# commande.net
KiCad netlist of a schematic drawn in Altium Designer
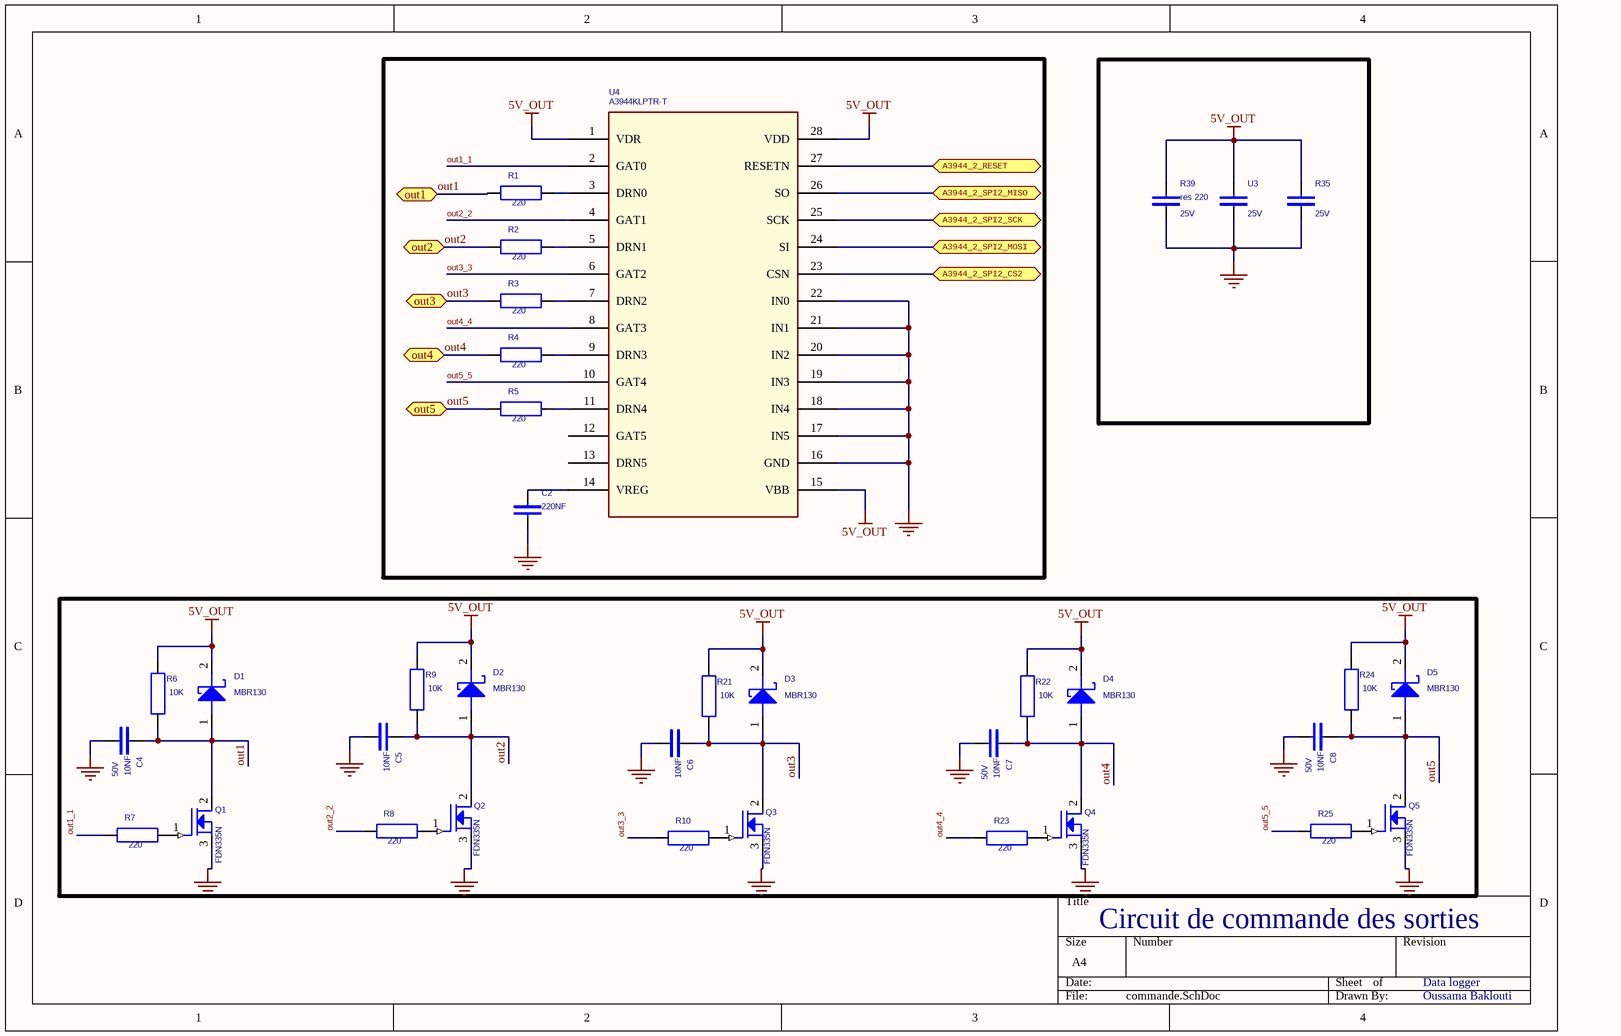
[diagram p0: commande.SchDoc]

(export (version "E")
  (design (tool "Eeschema 10.0.6"))
  (components
    (comp (ref "C2")
      (value "220NF")
      (footprint "cap 220uF 50v")
      (description "Aluminium Electrolytic Capacitors - SMD 50volts 0.22uF AEC-Q200")
      (fields (field (name "MFR") "Nichicon"))
      (libsource (lib "*") (part "CAPA_Dup1"))
    )
    (comp (ref "C4")
      (value "10NF")
      (footprint "cap 10nF 50V")
      (description "10000 pF ±10% 50V Ceramic Capacitor X7R 0402 (1005 Metric)")
      (fields
        (field (name "VOLTAGE") "50V")
        (field (name "PART NUMBER") "AY15800014")
        (field (name "TOLERANCE") "10%")
      )
      (libsource (lib "*") (part "CAPA_Dup1"))
    )
    (comp (ref "C5")
      (value "10NF")
      (footprint "cap 10nF 50V")
      (description "10000 pF ±10% 50V Ceramic Capacitor X7R 0402 (1005 Metric)")
      (fields (field (name "MFR") "Murata Electronics"))
      (libsource (lib "*") (part "CAPA_Dup1"))
    )
    (comp (ref "C6")
      (value "10NF")
      (footprint "cap 10nF 50V")
      (description "10000 pF ±10% 50V Ceramic Capacitor X7R 0402 (1005 Metric)")
      (fields (field (name "MFR") "Murata Electronics"))
      (libsource (lib "*") (part "CAPA_Dup1"))
    )
    (comp (ref "C7")
      (value "10NF")
      (footprint "cap 10nF 50V")
      (description "10000 pF ±10% 50V Ceramic Capacitor X7R 0402 (1005 Metric)")
      (fields
        (field (name "VOLTAGE") "50V")
        (field (name "PART NUMBER") "AY15800014")
        (field (name "TOLERANCE") "10%")
      )
      (libsource (lib "*") (part "CAPA_Dup1"))
    )
    (comp (ref "C8")
      (value "10NF")
      (footprint "cap 10nF 50V")
      (description "10000 pF ±10% 50V Ceramic Capacitor X7R 0402 (1005 Metric)")
      (fields
        (field (name "VOLTAGE") "50V")
        (field (name "PART NUMBER") "AY15800014")
        (field (name "TOLERANCE") "10%")
      )
      (libsource (lib "*") (part "CAPA_Dup1"))
    )
    (comp (ref "D1")
      (value "MBR130")
      (footprint "diode skotty")
      (description "Schottky Diodes & Rectifiers 1A 30V")
      (fields (field (name "MFR") "onsemi"))
      (libsource (lib "*") (part "DIODE_SCHOT"))
    )
    (comp (ref "D2")
      (value "MBR130")
      (footprint "diode skotty")
      (description "Schottky Diodes & Rectifiers 1A 30V")
      (fields (field (name "MFR") "onsemi"))
      (libsource (lib "*") (part "DIODE_SCHOT"))
    )
    (comp (ref "D3")
      (value "MBR130")
      (footprint "diode skotty")
      (description "Schottky Diodes & Rectifiers 1A 30V")
      (fields (field (name "MFR") "onsemi"))
      (libsource (lib "*") (part "DIODE_SCHOT"))
    )
    (comp (ref "D4")
      (value "MBR130")
      (footprint "diode skotty")
      (description "Schottky Diodes & Rectifiers 1A 30V")
      (fields (field (name "MFR") "onsemi"))
      (libsource (lib "*") (part "DIODE_SCHOT"))
    )
    (comp (ref "D5")
      (value "MBR130")
      (footprint "diode skotty")
      (description "Schottky Diodes & Rectifiers 1A 30V")
      (fields (field (name "MFR") "onsemi"))
      (libsource (lib "*") (part "DIODE_SCHOT"))
    )
    (comp (ref "Q1")
      (value "FDN335N")
      (footprint "FDN335N")
      (description "MOSFET SSOT-3 N-CH 20V")
      (fields (field (name "MFR") "onsemi / Fairchild"))
      (libsource (lib "*") (part "MOSFET N"))
    )
    (comp (ref "Q2")
      (value "FDN335N")
      (footprint "FDN335N")
      (description "MOSFET SSOT-3 N-CH 20V")
      (fields (field (name "MFR") "onsemi / Fairchild"))
      (libsource (lib "*") (part "MOSFET N"))
    )
    (comp (ref "Q3")
      (value "FDN335N")
      (footprint "FDN335N")
      (description "MOSFET SSOT-3 N-CH 20V")
      (fields (field (name "MFR") "onsemi / Fairchild"))
      (libsource (lib "*") (part "MOSFET N"))
    )
    (comp (ref "Q4")
      (value "FDN335N")
      (footprint "FDN335N")
      (description "MOSFET SSOT-3 N-CH 20V")
      (fields (field (name "MFR") "onsemi / Fairchild"))
      (libsource (lib "*") (part "MOSFET N"))
    )
    (comp (ref "Q5")
      (value "FDN335N")
      (footprint "FDN335N")
      (description "MOSFET SSOT-3 N-CH 20V")
      (fields (field (name "MFR") "onsemi / Fairchild"))
      (libsource (lib "*") (part "MOSFET N"))
    )
    (comp (ref "R1")
      (value "220")
      (footprint "res 220")
      (description "Thick Film Resistors - SMD 1/2watt 220ohms 1% High Power AEC-Q200")
      (fields (field (name "MFR") "Vishay / Dale"))
      (libsource (lib "*") (part "RE"))
    )
    (comp (ref "R2")
      (value "220")
      (footprint "res 220")
      (description "Thick Film Resistors - SMD 1/2watt 220ohms 1% High Power AEC-Q200")
      (fields (field (name "MFR") "Vishay / Dale"))
      (libsource (lib "*") (part "RE"))
    )
    (comp (ref "R3")
      (value "220")
      (footprint "res 220")
      (description "Thick Film Resistors - SMD 1/2watt 220ohms 1% High Power AEC-Q200")
      (fields (field (name "MFR") "Vishay / Dale"))
      (libsource (lib "*") (part "RE"))
    )
    (comp (ref "R4")
      (value "220")
      (footprint "res 220")
      (description "Thick Film Resistors - SMD 1/2watt 220ohms 1% High Power AEC-Q200")
      (fields (field (name "MFR") "Vishay / Dale"))
      (libsource (lib "*") (part "RE"))
    )
    (comp (ref "R5")
      (value "220")
      (footprint "res 220")
      (description "Thick Film Resistors - SMD 1/2watt 220ohms 1% High Power AEC-Q200")
      (fields (field (name "MFR") "Vishay / Dale"))
      (libsource (lib "*") (part "RE"))
    )
    (comp (ref "R6")
      (value "10K")
      (footprint "RES_10k")
      (description "Thick Film Resistors - SMD ResHighPowerA 0805 10k 1% 1/2W TC100")
      (fields (field (name "MFR") "Bourns"))
      (libsource (lib "*") (part "RE"))
    )
    (comp (ref "R7")
      (value "220")
      (footprint "res 220")
      (description "Thick Film Resistors - SMD 1/2watt 220ohms 1% High Power AEC-Q200")
      (fields (field (name "MFR") "Vishay / Dale"))
      (libsource (lib "*") (part "RE"))
    )
    (comp (ref "R8")
      (value "220")
      (footprint "res 220")
      (description "Thick Film Resistors - SMD 1/2watt 220ohms 1% High Power AEC-Q200")
      (fields (field (name "MFR") "Vishay / Dale"))
      (libsource (lib "*") (part "RE"))
    )
    (comp (ref "R9")
      (value "10K")
      (footprint "RES_10k")
      (description "Thick Film Resistors - SMD ResHighPowerA 0805 10k 1% 1/2W TC100")
      (fields (field (name "MFR") "Bourns"))
      (libsource (lib "*") (part "RE"))
    )
    (comp (ref "R10")
      (value "220")
      (footprint "res 220")
      (description "Thick Film Resistors - SMD 1/2watt 220ohms 1% High Power AEC-Q200")
      (fields (field (name "MFR") "Vishay / Dale"))
      (libsource (lib "*") (part "RE"))
    )
    (comp (ref "R21")
      (value "10K")
      (footprint "RES_10k")
      (description "Thick Film Resistors - SMD ResHighPowerA 0805 10k 1% 1/2W TC100")
      (fields (field (name "MFR") "Bourns"))
      (libsource (lib "*") (part "RE"))
    )
    (comp (ref "R22")
      (value "10K")
      (footprint "RES_10k")
      (description "Thick Film Resistors - SMD ResHighPowerA 0805 10k 1% 1/2W TC100")
      (fields (field (name "MFR") "Bourns"))
      (libsource (lib "*") (part "RE"))
    )
    (comp (ref "R23")
      (value "220")
      (footprint "res 220")
      (description "Thick Film Resistors - SMD 1/2watt 220ohms 1% High Power AEC-Q200")
      (fields (field (name "MFR") "Vishay / Dale"))
      (libsource (lib "*") (part "RE"))
    )
    (comp (ref "R24")
      (value "10K")
      (footprint "RES_10k")
      (description "Thick Film Resistors - SMD ResHighPowerA 0805 10k 1% 1/2W TC100")
      (fields (field (name "MFR") "Bourns"))
      (libsource (lib "*") (part "RE"))
    )
    (comp (ref "R25")
      (value "220")
      (footprint "res 220")
      (description "Thick Film Resistors - SMD 1/2watt 220ohms 1% High Power AEC-Q200")
      (fields (field (name "MFR") "Vishay / Dale"))
      (libsource (lib "*") (part "RE"))
    )
    (comp (ref "R35")
      (value "~")
      (footprint "RES 220")
      (fields
        (field (name "VOLTAGE") "25V")
        (field (name "TOLERANCE") "10%")
        (field (name "PART NUMBER") "AY15620002")
      )
      (libsource (lib "*") (part "CAPA_Dup1"))
    )
    (comp (ref "R39")
      (value "res 220")
      (footprint "RES 220")
      (fields
        (field (name "VOLTAGE") "25V")
        (field (name "TOLERANCE") "10%")
        (field (name "PART NUMBER") "AY15510021")
      )
      (libsource (lib "*") (part "CAPA_Dup1"))
    )
    (comp (ref "U3")
      (value "~")
      (footprint "LILYGO-T-CALL-SIM800L")
      (fields
        (field (name "VOLTAGE") "25V")
        (field (name "TOLERANCE") "10%")
        (field (name "PART NUMBER") "AY15620002")
      )
      (libsource (lib "*") (part "CAPA_Dup1"))
    )
    (comp (ref "U4")
      (value "A3944KLPTR-T")
      (footprint "SOP65P640X265_HS-29N")
      (description "Motor/Motion/Ignition Controllers & Drivers AUTOMOTIVE SIX CHANNEL LOW SIDE MOSFET PRE-DRIVER")
      (fields (field (name "MFR") "Mfr.:Allegro MicroSystems"))
      (libsource (lib "*") (part "A3944KLPTR-T"))
    )
  )
  (nets
    (net (code "1") (name "/A3944_2_RESET") (class "Default")
      (node (ref "U4") (pin "27") (pinfunction "RESETN_27") (pintype "passive"))
    )
    (net (code "2") (name "/A3944_2_SPI2_CS2") (class "Default")
      (node (ref "U4") (pin "23") (pinfunction "CSN_23") (pintype "passive"))
    )
    (net (code "3") (name "/A3944_2_SPI2_MISO") (class "Default")
      (node (ref "U4") (pin "26") (pinfunction "SO_26") (pintype "passive"))
    )
    (net (code "4") (name "/A3944_2_SPI2_MOSI") (class "Default")
      (node (ref "U4") (pin "24") (pinfunction "SI_24") (pintype "passive"))
    )
    (net (code "5") (name "/A3944_2_SPI2_SCK") (class "Default")
      (node (ref "U4") (pin "25") (pinfunction "SCK_25") (pintype "passive"))
    )
    (net (code "6") (name "/out1") (class "Default")
      (node (ref "C4") (pin "1") (pinfunction "1_1") (pintype "passive"))
      (node (ref "D1") (pin "1") (pinfunction "A_1") (pintype "passive"))
      (node (ref "Q1") (pin "2") (pinfunction "DRAIN_2") (pintype "passive"))
      (node (ref "R1") (pin "2") (pinfunction "2_2") (pintype "passive"))
      (node (ref "R6") (pin "2") (pinfunction "2_2") (pintype "passive"))
    )
    (net (code "7") (name "/out1_1") (class "Default")
      (node (ref "R7") (pin "2") (pinfunction "2_2") (pintype "passive"))
      (node (ref "U4") (pin "2") (pinfunction "GAT0_2") (pintype "passive"))
    )
    (net (code "8") (name "/out2") (class "Default")
      (node (ref "C5") (pin "1") (pinfunction "1_1") (pintype "passive"))
      (node (ref "D2") (pin "1") (pinfunction "A_1") (pintype "passive"))
      (node (ref "Q2") (pin "2") (pinfunction "DRAIN_2") (pintype "passive"))
      (node (ref "R2") (pin "2") (pinfunction "2_2") (pintype "passive"))
      (node (ref "R9") (pin "2") (pinfunction "2_2") (pintype "passive"))
    )
    (net (code "9") (name "/out2_2") (class "Default")
      (node (ref "R8") (pin "2") (pinfunction "2_2") (pintype "passive"))
      (node (ref "U4") (pin "4") (pinfunction "GAT1_4") (pintype "passive"))
    )
    (net (code "10") (name "/out3") (class "Default")
      (node (ref "C6") (pin "1") (pinfunction "1_1") (pintype "passive"))
      (node (ref "D3") (pin "1") (pinfunction "A_1") (pintype "passive"))
      (node (ref "Q3") (pin "2") (pinfunction "DRAIN_2") (pintype "passive"))
      (node (ref "R21") (pin "2") (pinfunction "2_2") (pintype "passive"))
      (node (ref "R3") (pin "2") (pinfunction "2_2") (pintype "passive"))
    )
    (net (code "11") (name "/out3_3") (class "Default")
      (node (ref "R10") (pin "2") (pinfunction "2_2") (pintype "passive"))
      (node (ref "U4") (pin "6") (pinfunction "GAT2_6") (pintype "passive"))
    )
    (net (code "12") (name "/out4") (class "Default")
      (node (ref "C7") (pin "1") (pinfunction "1_1") (pintype "passive"))
      (node (ref "D4") (pin "1") (pinfunction "A_1") (pintype "passive"))
      (node (ref "Q4") (pin "2") (pinfunction "DRAIN_2") (pintype "passive"))
      (node (ref "R22") (pin "2") (pinfunction "2_2") (pintype "passive"))
      (node (ref "R4") (pin "2") (pinfunction "2_2") (pintype "passive"))
    )
    (net (code "13") (name "/out4_4") (class "Default")
      (node (ref "R23") (pin "2") (pinfunction "2_2") (pintype "passive"))
      (node (ref "U4") (pin "8") (pinfunction "GAT3_8") (pintype "passive"))
    )
    (net (code "14") (name "/out5") (class "Default")
      (node (ref "C8") (pin "1") (pinfunction "1_1") (pintype "passive"))
      (node (ref "D5") (pin "1") (pinfunction "A_1") (pintype "passive"))
      (node (ref "Q5") (pin "2") (pinfunction "DRAIN_2") (pintype "passive"))
      (node (ref "R24") (pin "2") (pinfunction "2_2") (pintype "passive"))
      (node (ref "R5") (pin "2") (pinfunction "2_2") (pintype "passive"))
    )
    (net (code "15") (name "/out5_5") (class "Default")
      (node (ref "R25") (pin "2") (pinfunction "2_2") (pintype "passive"))
      (node (ref "U4") (pin "10") (pinfunction "GAT4_10") (pintype "passive"))
    )
    (net (code "16") (name "5V_OUT") (class "Default")
      (node (ref "D1") (pin "2") (pinfunction "K_2") (pintype "passive"))
      (node (ref "D2") (pin "2") (pinfunction "K_2") (pintype "passive"))
      (node (ref "D3") (pin "2") (pinfunction "K_2") (pintype "passive"))
      (node (ref "D4") (pin "2") (pinfunction "K_2") (pintype "passive"))
      (node (ref "D5") (pin "2") (pinfunction "K_2") (pintype "passive"))
      (node (ref "R21") (pin "1") (pinfunction "1_1") (pintype "passive"))
      (node (ref "R22") (pin "1") (pinfunction "1_1") (pintype "passive"))
      (node (ref "R24") (pin "1") (pinfunction "1_1") (pintype "passive"))
      (node (ref "R35") (pin "1") (pinfunction "1_1") (pintype "passive"))
      (node (ref "R39") (pin "1") (pinfunction "1_1") (pintype "passive"))
      (node (ref "R6") (pin "1") (pinfunction "1_1") (pintype "passive"))
      (node (ref "R9") (pin "1") (pinfunction "1_1") (pintype "passive"))
      (node (ref "U3") (pin "1") (pinfunction "1_1") (pintype "passive"))
      (node (ref "U4") (pin "1") (pinfunction "VDR_1") (pintype "passive"))
      (node (ref "U4") (pin "15") (pinfunction "VBB_15") (pintype "passive"))
      (node (ref "U4") (pin "28") (pinfunction "VDD_28") (pintype "passive"))
    )
    (net (code "17") (name "GND") (class "Default")
      (node (ref "C2") (pin "2") (pinfunction "2_2") (pintype "passive"))
      (node (ref "C4") (pin "2") (pinfunction "2_2") (pintype "passive"))
      (node (ref "C5") (pin "2") (pinfunction "2_2") (pintype "passive"))
      (node (ref "C6") (pin "2") (pinfunction "2_2") (pintype "passive"))
      (node (ref "C7") (pin "2") (pinfunction "2_2") (pintype "passive"))
      (node (ref "C8") (pin "2") (pinfunction "2_2") (pintype "passive"))
      (node (ref "Q1") (pin "3") (pinfunction "SOURCE_3") (pintype "passive"))
      (node (ref "Q2") (pin "3") (pinfunction "SOURCE_3") (pintype "passive"))
      (node (ref "Q3") (pin "3") (pinfunction "SOURCE_3") (pintype "passive"))
      (node (ref "Q4") (pin "3") (pinfunction "SOURCE_3") (pintype "passive"))
      (node (ref "Q5") (pin "3") (pinfunction "SOURCE_3") (pintype "passive"))
      (node (ref "R35") (pin "2") (pinfunction "2_2") (pintype "passive"))
      (node (ref "R39") (pin "2") (pinfunction "2_2") (pintype "passive"))
      (node (ref "U3") (pin "2") (pinfunction "2_2") (pintype "passive"))
      (node (ref "U4") (pin "16") (pinfunction "GND_16") (pintype "passive"))
      (node (ref "U4") (pin "17") (pinfunction "IN5_17") (pintype "passive"))
      (node (ref "U4") (pin "18") (pinfunction "IN4_18") (pintype "passive"))
      (node (ref "U4") (pin "19") (pinfunction "IN3_19") (pintype "passive"))
      (node (ref "U4") (pin "20") (pinfunction "IN2_20") (pintype "passive"))
      (node (ref "U4") (pin "21") (pinfunction "IN1_21") (pintype "passive"))
      (node (ref "U4") (pin "22") (pinfunction "IN0_22") (pintype "passive"))
    )
    (net (code "18") (name "Net-(Q1-GATE)") (class "Default")
      (node (ref "Q1") (pin "1") (pinfunction "GATE_1") (pintype "input"))
      (node (ref "R7") (pin "1") (pinfunction "1_1") (pintype "passive"))
    )
    (net (code "19") (name "Net-(Q2-GATE)") (class "Default")
      (node (ref "Q2") (pin "1") (pinfunction "GATE_1") (pintype "input"))
      (node (ref "R8") (pin "1") (pinfunction "1_1") (pintype "passive"))
    )
    (net (code "20") (name "Net-(Q3-GATE)") (class "Default")
      (node (ref "Q3") (pin "1") (pinfunction "GATE_1") (pintype "input"))
      (node (ref "R10") (pin "1") (pinfunction "1_1") (pintype "passive"))
    )
    (net (code "21") (name "Net-(Q4-GATE)") (class "Default")
      (node (ref "Q4") (pin "1") (pinfunction "GATE_1") (pintype "input"))
      (node (ref "R23") (pin "1") (pinfunction "1_1") (pintype "passive"))
    )
    (net (code "22") (name "Net-(Q5-GATE)") (class "Default")
      (node (ref "Q5") (pin "1") (pinfunction "GATE_1") (pintype "input"))
      (node (ref "R25") (pin "1") (pinfunction "1_1") (pintype "passive"))
    )
    (net (code "23") (name "Net-(U4-DRN0)") (class "Default")
      (node (ref "R1") (pin "1") (pinfunction "1_1") (pintype "passive"))
      (node (ref "U4") (pin "3") (pinfunction "DRN0_3") (pintype "passive"))
    )
    (net (code "24") (name "Net-(U4-DRN1)") (class "Default")
      (node (ref "R2") (pin "1") (pinfunction "1_1") (pintype "passive"))
      (node (ref "U4") (pin "5") (pinfunction "DRN1_5") (pintype "passive"))
    )
    (net (code "25") (name "Net-(U4-DRN2)") (class "Default")
      (node (ref "R3") (pin "1") (pinfunction "1_1") (pintype "passive"))
      (node (ref "U4") (pin "7") (pinfunction "DRN2_7") (pintype "passive"))
    )
    (net (code "26") (name "Net-(U4-DRN3)") (class "Default")
      (node (ref "R4") (pin "1") (pinfunction "1_1") (pintype "passive"))
      (node (ref "U4") (pin "9") (pinfunction "DRN3_9") (pintype "passive"))
    )
    (net (code "27") (name "Net-(U4-DRN4)") (class "Default")
      (node (ref "R5") (pin "1") (pinfunction "1_1") (pintype "passive"))
      (node (ref "U4") (pin "11") (pinfunction "DRN4_11") (pintype "passive"))
    )
    (net (code "28") (name "Net-(U4-VREG)") (class "Default")
      (node (ref "C2") (pin "1") (pinfunction "1_1") (pintype "passive"))
      (node (ref "U4") (pin "14") (pinfunction "VREG_14") (pintype "passive"))
    )
    (net (code "29") (name "unconnected-(U4-DRN5-Pad13)") (class "Default")
      (node (ref "U4") (pin "13") (pinfunction "DRN5_13") (pintype "passive"))
    )
    (net (code "30") (name "unconnected-(U4-GAT5-Pad12)") (class "Default")
      (node (ref "U4") (pin "12") (pinfunction "GAT5_12") (pintype "passive"))
    )
  )
)
